# mutebox.net
KiCad netlist of a schematic drawn in EAGLE
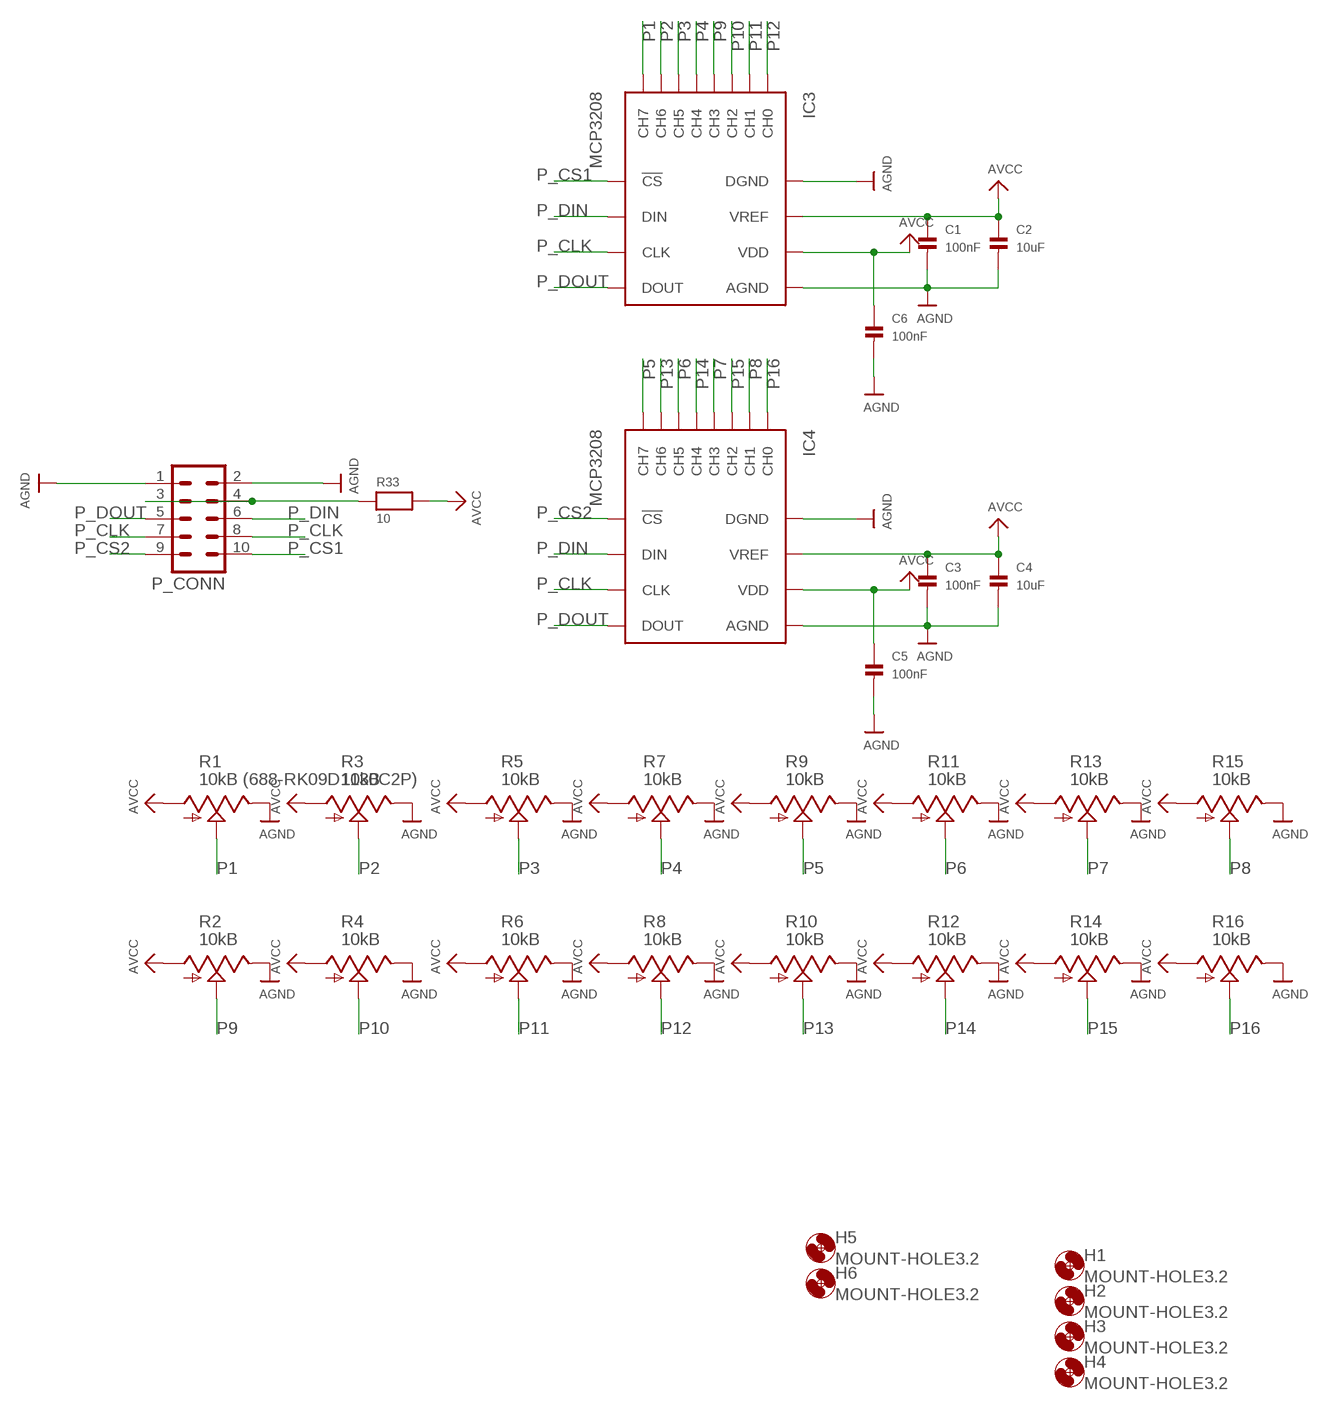
[diagram p0: schematic, sheet 1]
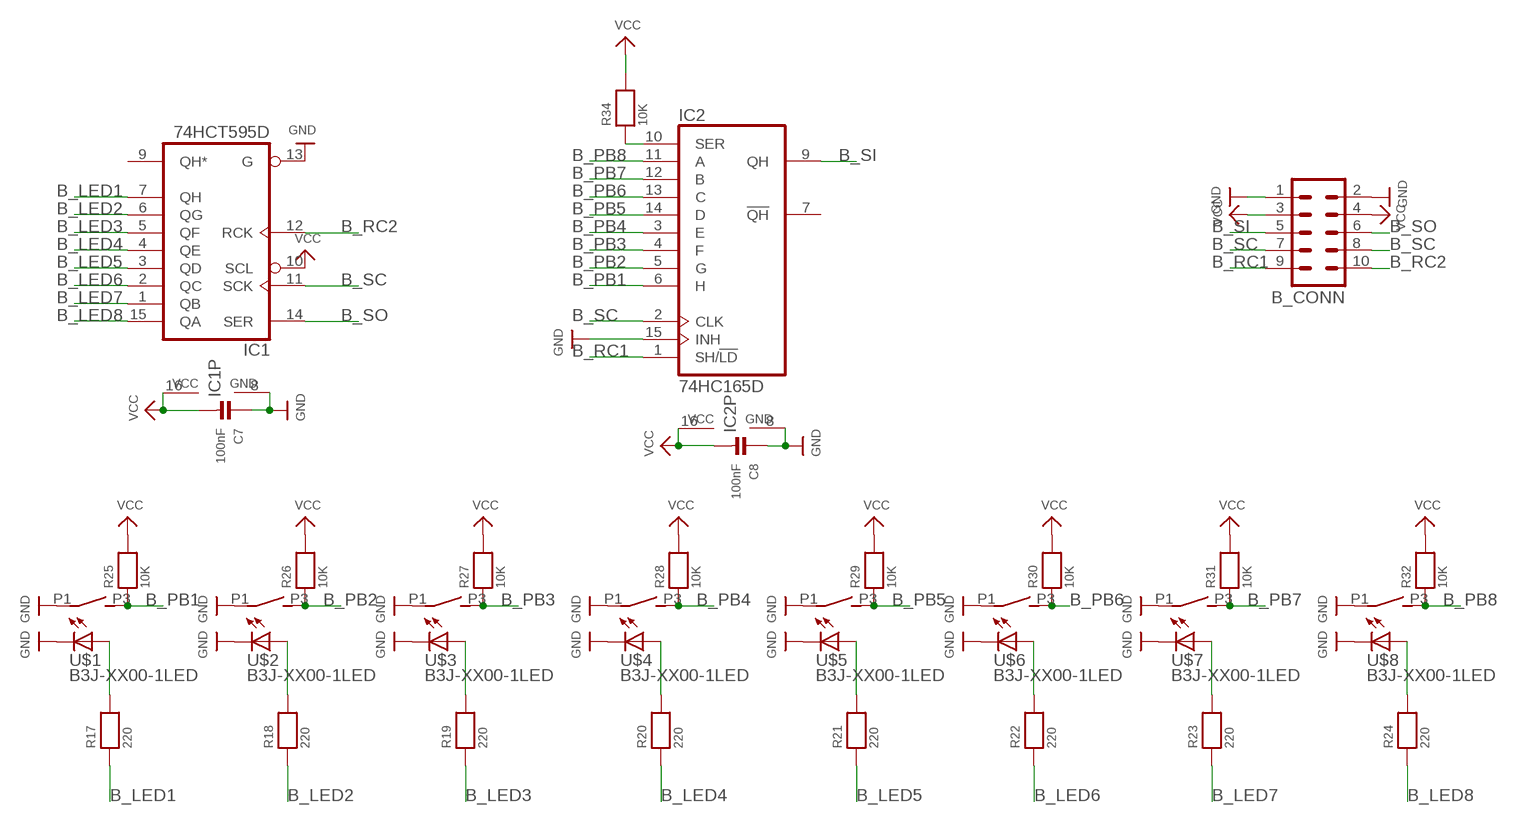
[diagram p1: schematic, sheet 2]

(export (version "E")
  (design (tool "Eeschema 10.0.6"))
  (components
    (comp (ref "C1")
      (value "100nF")
      (footprint "eagle-import:0603")
      (libsource (lib "eagle-import") (part "CAP_CERAMIC0603"))
    )
    (comp (ref "C2")
      (value "10uF")
      (footprint "eagle-import:_0805")
      (libsource (lib "eagle-import") (part "CAP_CERAMIC_0805"))
    )
    (comp (ref "C3")
      (value "100nF")
      (footprint "eagle-import:0603")
      (libsource (lib "eagle-import") (part "CAP_CERAMIC0603"))
    )
    (comp (ref "C4")
      (value "10uF")
      (footprint "eagle-import:_0805")
      (libsource (lib "eagle-import") (part "CAP_CERAMIC_0805"))
    )
    (comp (ref "C5")
      (value "100nF")
      (footprint "eagle-import:0603")
      (libsource (lib "eagle-import") (part "CAP_CERAMIC0603"))
    )
    (comp (ref "C6")
      (value "100nF")
      (footprint "eagle-import:0603")
      (libsource (lib "eagle-import") (part "CAP_CERAMIC0603"))
    )
    (comp (ref "H1")
      (value "MOUNT-HOLE3.2")
      (footprint "eagle-import:3,2")
      (libsource (lib "eagle-import") (part "MOUNT-HOLE3.2"))
    )
    (comp (ref "H2")
      (value "MOUNT-HOLE3.2")
      (footprint "eagle-import:3,2")
      (libsource (lib "eagle-import") (part "MOUNT-HOLE3.2"))
    )
    (comp (ref "H3")
      (value "MOUNT-HOLE3.2")
      (footprint "eagle-import:3,2")
      (libsource (lib "eagle-import") (part "MOUNT-HOLE3.2"))
    )
    (comp (ref "H4")
      (value "MOUNT-HOLE3.2")
      (footprint "eagle-import:3,2")
      (libsource (lib "eagle-import") (part "MOUNT-HOLE3.2"))
    )
    (comp (ref "H5")
      (value "MOUNT-HOLE3.2")
      (footprint "eagle-import:3,2")
      (libsource (lib "eagle-import") (part "MOUNT-HOLE3.2"))
    )
    (comp (ref "H6")
      (value "MOUNT-HOLE3.2")
      (footprint "eagle-import:3,2")
      (libsource (lib "eagle-import") (part "MOUNT-HOLE3.2"))
    )
    (comp (ref "IC3")
      (value "MCP3208")
      (footprint "eagle-import:PDIP16")
      (libsource (lib "eagle-import") (part "21298E"))
    )
    (comp (ref "IC4")
      (value "MCP3208")
      (footprint "eagle-import:PDIP16")
      (libsource (lib "eagle-import") (part "21298E"))
    )
    (comp (ref "P_CONN")
      (value "ML10")
      (footprint "eagle-import:ML10")
      (libsource (lib "eagle-import") (part "ML10"))
    )
    (comp (ref "R1")
      (value "10kB (688-RK09D1130C2P)")
      (footprint "eagle-import:ALPS_POT_VERTICAL_PS")
      (libsource (lib "eagle-import") (part "POT_USVERTICAL_PS"))
    )
    (comp (ref "R2")
      (value "10kB")
      (footprint "eagle-import:ALPS_POT_VERTICAL_PS")
      (libsource (lib "eagle-import") (part "POT_USVERTICAL_PS"))
    )
    (comp (ref "R3")
      (value "10kB")
      (footprint "eagle-import:ALPS_POT_VERTICAL_PS")
      (libsource (lib "eagle-import") (part "POT_USVERTICAL_PS"))
    )
    (comp (ref "R4")
      (value "10kB")
      (footprint "eagle-import:ALPS_POT_VERTICAL_PS")
      (libsource (lib "eagle-import") (part "POT_USVERTICAL_PS"))
    )
    (comp (ref "R5")
      (value "10kB")
      (footprint "eagle-import:ALPS_POT_VERTICAL_PS")
      (libsource (lib "eagle-import") (part "POT_USVERTICAL_PS"))
    )
    (comp (ref "R6")
      (value "10kB")
      (footprint "eagle-import:ALPS_POT_VERTICAL_PS")
      (libsource (lib "eagle-import") (part "POT_USVERTICAL_PS"))
    )
    (comp (ref "R7")
      (value "10kB")
      (footprint "eagle-import:ALPS_POT_VERTICAL_PS")
      (libsource (lib "eagle-import") (part "POT_USVERTICAL_PS"))
    )
    (comp (ref "R8")
      (value "10kB")
      (footprint "eagle-import:ALPS_POT_VERTICAL_PS")
      (libsource (lib "eagle-import") (part "POT_USVERTICAL_PS"))
    )
    (comp (ref "R9")
      (value "10kB")
      (footprint "eagle-import:ALPS_POT_VERTICAL_PS")
      (libsource (lib "eagle-import") (part "POT_USVERTICAL_PS"))
    )
    (comp (ref "R10")
      (value "10kB")
      (footprint "eagle-import:ALPS_POT_VERTICAL_PS")
      (libsource (lib "eagle-import") (part "POT_USVERTICAL_PS"))
    )
    (comp (ref "R11")
      (value "10kB")
      (footprint "eagle-import:ALPS_POT_VERTICAL_PS")
      (libsource (lib "eagle-import") (part "POT_USVERTICAL_PS"))
    )
    (comp (ref "R12")
      (value "10kB")
      (footprint "eagle-import:ALPS_POT_VERTICAL_PS")
      (libsource (lib "eagle-import") (part "POT_USVERTICAL_PS"))
    )
    (comp (ref "R13")
      (value "10kB")
      (footprint "eagle-import:ALPS_POT_VERTICAL_PS")
      (libsource (lib "eagle-import") (part "POT_USVERTICAL_PS"))
    )
    (comp (ref "R14")
      (value "10kB")
      (footprint "eagle-import:ALPS_POT_VERTICAL_PS")
      (libsource (lib "eagle-import") (part "POT_USVERTICAL_PS"))
    )
    (comp (ref "R15")
      (value "10kB")
      (footprint "eagle-import:ALPS_POT_VERTICAL_PS")
      (libsource (lib "eagle-import") (part "POT_USVERTICAL_PS"))
    )
    (comp (ref "R16")
      (value "10kB")
      (footprint "eagle-import:ALPS_POT_VERTICAL_PS")
      (libsource (lib "eagle-import") (part "POT_USVERTICAL_PS"))
    )
    (comp (ref "R33")
      (value "10")
      (footprint "eagle-import:_0805")
      (libsource (lib "eagle-import") (part "RESISTOR_0805"))
    )
    (comp (ref "B_CONN")
      (value "ML10")
      (footprint "eagle-import:ML10")
      (libsource (lib "eagle-import") (part "ML10"))
    )
    (comp (ref "C7")
      (value "100nF")
      (footprint "eagle-import:0603")
      (libsource (lib "eagle-import") (part "CAP_CERAMIC0603"))
    )
    (comp (ref "C8")
      (value "100nF")
      (footprint "eagle-import:0603")
      (libsource (lib "eagle-import") (part "CAP_CERAMIC0603"))
    )
    (comp (ref "IC1")
      (value "74HCT595D")
      (footprint "eagle-import:SO16")
      (libsource (lib "eagle-import") (part "74595DHCT"))
    )
    (comp (ref "IC2")
      (value "74HC165D")
      (footprint "eagle-import:SO16")
      (libsource (lib "eagle-import") (part "74165DHC"))
    )
    (comp (ref "R17")
      (value "220")
      (footprint "eagle-import:_0603")
      (libsource (lib "eagle-import") (part "RESISTOR_0603"))
    )
    (comp (ref "R18")
      (value "220")
      (footprint "eagle-import:_0603")
      (libsource (lib "eagle-import") (part "RESISTOR_0603"))
    )
    (comp (ref "R19")
      (value "220")
      (footprint "eagle-import:_0603")
      (libsource (lib "eagle-import") (part "RESISTOR_0603"))
    )
    (comp (ref "R20")
      (value "220")
      (footprint "eagle-import:_0603")
      (libsource (lib "eagle-import") (part "RESISTOR_0603"))
    )
    (comp (ref "R21")
      (value "220")
      (footprint "eagle-import:_0603")
      (libsource (lib "eagle-import") (part "RESISTOR_0603"))
    )
    (comp (ref "R22")
      (value "220")
      (footprint "eagle-import:_0603")
      (libsource (lib "eagle-import") (part "RESISTOR_0603"))
    )
    (comp (ref "R23")
      (value "220")
      (footprint "eagle-import:_0603")
      (libsource (lib "eagle-import") (part "RESISTOR_0603"))
    )
    (comp (ref "R24")
      (value "220")
      (footprint "eagle-import:_0603")
      (libsource (lib "eagle-import") (part "RESISTOR_0603"))
    )
    (comp (ref "R25")
      (value "10K")
      (footprint "eagle-import:_0603")
      (libsource (lib "eagle-import") (part "RESISTOR_0603"))
    )
    (comp (ref "R26")
      (value "10K")
      (footprint "eagle-import:_0603")
      (libsource (lib "eagle-import") (part "RESISTOR_0603"))
    )
    (comp (ref "R27")
      (value "10K")
      (footprint "eagle-import:_0603")
      (libsource (lib "eagle-import") (part "RESISTOR_0603"))
    )
    (comp (ref "R28")
      (value "10K")
      (footprint "eagle-import:_0603")
      (libsource (lib "eagle-import") (part "RESISTOR_0603"))
    )
    (comp (ref "R29")
      (value "10K")
      (footprint "eagle-import:_0603")
      (libsource (lib "eagle-import") (part "RESISTOR_0603"))
    )
    (comp (ref "R30")
      (value "10K")
      (footprint "eagle-import:_0603")
      (libsource (lib "eagle-import") (part "RESISTOR_0603"))
    )
    (comp (ref "R31")
      (value "10K")
      (footprint "eagle-import:_0603")
      (libsource (lib "eagle-import") (part "RESISTOR_0603"))
    )
    (comp (ref "R32")
      (value "10K")
      (footprint "eagle-import:_0603")
      (libsource (lib "eagle-import") (part "RESISTOR_0603"))
    )
    (comp (ref "R34")
      (value "10K")
      (footprint "eagle-import:_0603")
      (libsource (lib "eagle-import") (part "RESISTOR_0603"))
    )
    (comp (ref "U$1")
      (value "B3J-XX00-1LED")
      (footprint "eagle-import:B3J-XX00-1LED")
      (libsource (lib "eagle-import") (part "B3J-XX00-1LED"))
    )
    (comp (ref "U$2")
      (value "B3J-XX00-1LED")
      (footprint "eagle-import:B3J-XX00-1LED")
      (libsource (lib "eagle-import") (part "B3J-XX00-1LED"))
    )
    (comp (ref "U$3")
      (value "B3J-XX00-1LED")
      (footprint "eagle-import:B3J-XX00-1LED")
      (libsource (lib "eagle-import") (part "B3J-XX00-1LED"))
    )
    (comp (ref "U$4")
      (value "B3J-XX00-1LED")
      (footprint "eagle-import:B3J-XX00-1LED")
      (libsource (lib "eagle-import") (part "B3J-XX00-1LED"))
    )
    (comp (ref "U$5")
      (value "B3J-XX00-1LED")
      (footprint "eagle-import:B3J-XX00-1LED")
      (libsource (lib "eagle-import") (part "B3J-XX00-1LED"))
    )
    (comp (ref "U$6")
      (value "B3J-XX00-1LED")
      (footprint "eagle-import:B3J-XX00-1LED")
      (libsource (lib "eagle-import") (part "B3J-XX00-1LED"))
    )
    (comp (ref "U$7")
      (value "B3J-XX00-1LED")
      (footprint "eagle-import:B3J-XX00-1LED")
      (libsource (lib "eagle-import") (part "B3J-XX00-1LED"))
    )
    (comp (ref "U$8")
      (value "B3J-XX00-1LED")
      (footprint "eagle-import:B3J-XX00-1LED")
      (libsource (lib "eagle-import") (part "B3J-XX00-1LED"))
    )
  )
  (nets
    (net (code "1") (name "AGND") (class "Default")
      (node (ref "C1") (pin "2") (pinfunction "P$2_2") (pintype "passive"))
      (node (ref "C2") (pin "2") (pinfunction "P$2_2") (pintype "passive"))
      (node (ref "C3") (pin "2") (pinfunction "P$2_2") (pintype "passive"))
      (node (ref "C4") (pin "2") (pinfunction "P$2_2") (pintype "passive"))
      (node (ref "C5") (pin "2") (pinfunction "P$2_2") (pintype "passive"))
      (node (ref "C6") (pin "2") (pinfunction "P$2_2") (pintype "passive"))
      (node (ref "IC3") (pin "P$14") (pinfunction "AGND_P$14") (pintype "bidirectional"))
      (node (ref "IC3") (pin "P$9") (pinfunction "DGND_P$9") (pintype "bidirectional"))
      (node (ref "IC4") (pin "P$14") (pinfunction "AGND_P$14") (pintype "bidirectional"))
      (node (ref "IC4") (pin "P$9") (pinfunction "DGND_P$9") (pintype "bidirectional"))
      (node (ref "P_CONN") (pin "1") (pinfunction "1_1") (pintype "passive"))
      (node (ref "P_CONN") (pin "2") (pinfunction "2_2") (pintype "passive"))
      (node (ref "R1") (pin "P$1") (pinfunction "E_P$1") (pintype "passive"))
      (node (ref "R10") (pin "P$1") (pinfunction "E_P$1") (pintype "passive"))
      (node (ref "R11") (pin "P$1") (pinfunction "E_P$1") (pintype "passive"))
      (node (ref "R12") (pin "P$1") (pinfunction "E_P$1") (pintype "passive"))
      (node (ref "R13") (pin "P$1") (pinfunction "E_P$1") (pintype "passive"))
      (node (ref "R14") (pin "P$1") (pinfunction "E_P$1") (pintype "passive"))
      (node (ref "R15") (pin "P$1") (pinfunction "E_P$1") (pintype "passive"))
      (node (ref "R16") (pin "P$1") (pinfunction "E_P$1") (pintype "passive"))
      (node (ref "R2") (pin "P$1") (pinfunction "E_P$1") (pintype "passive"))
      (node (ref "R3") (pin "P$1") (pinfunction "E_P$1") (pintype "passive"))
      (node (ref "R4") (pin "P$1") (pinfunction "E_P$1") (pintype "passive"))
      (node (ref "R5") (pin "P$1") (pinfunction "E_P$1") (pintype "passive"))
      (node (ref "R6") (pin "P$1") (pinfunction "E_P$1") (pintype "passive"))
      (node (ref "R7") (pin "P$1") (pinfunction "E_P$1") (pintype "passive"))
      (node (ref "R8") (pin "P$1") (pinfunction "E_P$1") (pintype "passive"))
      (node (ref "R9") (pin "P$1") (pinfunction "E_P$1") (pintype "passive"))
    )
    (net (code "2") (name "AVCC") (class "Default")
      (node (ref "C1") (pin "1") (pinfunction "P$1_1") (pintype "passive"))
      (node (ref "C2") (pin "1") (pinfunction "P$1_1") (pintype "passive"))
      (node (ref "C3") (pin "1") (pinfunction "P$1_1") (pintype "passive"))
      (node (ref "C4") (pin "1") (pinfunction "P$1_1") (pintype "passive"))
      (node (ref "C5") (pin "1") (pinfunction "P$1_1") (pintype "passive"))
      (node (ref "C6") (pin "1") (pinfunction "P$1_1") (pintype "passive"))
      (node (ref "IC3") (pin "P$15") (pinfunction "VREF_P$15") (pintype "bidirectional"))
      (node (ref "IC3") (pin "P$16") (pinfunction "VDD_P$16") (pintype "bidirectional"))
      (node (ref "IC4") (pin "P$15") (pinfunction "VREF_P$15") (pintype "bidirectional"))
      (node (ref "IC4") (pin "P$16") (pinfunction "VDD_P$16") (pintype "bidirectional"))
      (node (ref "R1") (pin "P$3") (pinfunction "A_P$3") (pintype "passive"))
      (node (ref "R10") (pin "P$3") (pinfunction "A_P$3") (pintype "passive"))
      (node (ref "R11") (pin "P$3") (pinfunction "A_P$3") (pintype "passive"))
      (node (ref "R12") (pin "P$3") (pinfunction "A_P$3") (pintype "passive"))
      (node (ref "R13") (pin "P$3") (pinfunction "A_P$3") (pintype "passive"))
      (node (ref "R14") (pin "P$3") (pinfunction "A_P$3") (pintype "passive"))
      (node (ref "R15") (pin "P$3") (pinfunction "A_P$3") (pintype "passive"))
      (node (ref "R16") (pin "P$3") (pinfunction "A_P$3") (pintype "passive"))
      (node (ref "R2") (pin "P$3") (pinfunction "A_P$3") (pintype "passive"))
      (node (ref "R3") (pin "P$3") (pinfunction "A_P$3") (pintype "passive"))
      (node (ref "R33") (pin "2") (pinfunction "2_2") (pintype "passive"))
      (node (ref "R4") (pin "P$3") (pinfunction "A_P$3") (pintype "passive"))
      (node (ref "R5") (pin "P$3") (pinfunction "A_P$3") (pintype "passive"))
      (node (ref "R6") (pin "P$3") (pinfunction "A_P$3") (pintype "passive"))
      (node (ref "R7") (pin "P$3") (pinfunction "A_P$3") (pintype "passive"))
      (node (ref "R8") (pin "P$3") (pinfunction "A_P$3") (pintype "passive"))
      (node (ref "R9") (pin "P$3") (pinfunction "A_P$3") (pintype "passive"))
    )
    (net (code "3") (name "B_LED1") (class "Default")
      (node (ref "IC1") (pin "7") (pinfunction "QH_7") (pintype "tri_state"))
      (node (ref "R17") (pin "1") (pinfunction "1_1") (pintype "passive"))
    )
    (net (code "4") (name "B_LED2") (class "Default")
      (node (ref "IC1") (pin "6") (pinfunction "QG_6") (pintype "tri_state"))
      (node (ref "R18") (pin "1") (pinfunction "1_1") (pintype "passive"))
    )
    (net (code "5") (name "B_LED3") (class "Default")
      (node (ref "IC1") (pin "5") (pinfunction "QF_5") (pintype "tri_state"))
      (node (ref "R19") (pin "1") (pinfunction "1_1") (pintype "passive"))
    )
    (net (code "6") (name "B_LED4") (class "Default")
      (node (ref "IC1") (pin "4") (pinfunction "QE_4") (pintype "tri_state"))
      (node (ref "R20") (pin "1") (pinfunction "1_1") (pintype "passive"))
    )
    (net (code "7") (name "B_LED5") (class "Default")
      (node (ref "IC1") (pin "3") (pinfunction "QD_3") (pintype "tri_state"))
      (node (ref "R21") (pin "1") (pinfunction "1_1") (pintype "passive"))
    )
    (net (code "8") (name "B_LED6") (class "Default")
      (node (ref "IC1") (pin "2") (pinfunction "QC_2") (pintype "tri_state"))
      (node (ref "R22") (pin "1") (pinfunction "1_1") (pintype "passive"))
    )
    (net (code "9") (name "B_LED7") (class "Default")
      (node (ref "IC1") (pin "1") (pinfunction "QB_1") (pintype "tri_state"))
      (node (ref "R23") (pin "1") (pinfunction "1_1") (pintype "passive"))
    )
    (net (code "10") (name "B_LED8") (class "Default")
      (node (ref "IC1") (pin "15") (pinfunction "QA_15") (pintype "tri_state"))
      (node (ref "R24") (pin "1") (pinfunction "1_1") (pintype "passive"))
    )
    (net (code "11") (name "B_PB1") (class "Default")
      (node (ref "IC2") (pin "6") (pinfunction "H_6") (pintype "input"))
      (node (ref "R25") (pin "1") (pinfunction "1_1") (pintype "passive"))
      (node (ref "U$1") (pin "P3") (pinfunction "SW2_P3") (pintype "passive"))
    )
    (net (code "12") (name "B_PB2") (class "Default")
      (node (ref "IC2") (pin "5") (pinfunction "G_5") (pintype "input"))
      (node (ref "R26") (pin "1") (pinfunction "1_1") (pintype "passive"))
      (node (ref "U$2") (pin "P3") (pinfunction "SW2_P3") (pintype "passive"))
    )
    (net (code "13") (name "B_PB3") (class "Default")
      (node (ref "IC2") (pin "4") (pinfunction "F_4") (pintype "input"))
      (node (ref "R27") (pin "1") (pinfunction "1_1") (pintype "passive"))
      (node (ref "U$3") (pin "P3") (pinfunction "SW2_P3") (pintype "passive"))
    )
    (net (code "14") (name "B_PB4") (class "Default")
      (node (ref "IC2") (pin "3") (pinfunction "E_3") (pintype "input"))
      (node (ref "R28") (pin "1") (pinfunction "1_1") (pintype "passive"))
      (node (ref "U$4") (pin "P3") (pinfunction "SW2_P3") (pintype "passive"))
    )
    (net (code "15") (name "B_PB5") (class "Default")
      (node (ref "IC2") (pin "14") (pinfunction "D_14") (pintype "input"))
      (node (ref "R29") (pin "1") (pinfunction "1_1") (pintype "passive"))
      (node (ref "U$5") (pin "P3") (pinfunction "SW2_P3") (pintype "passive"))
    )
    (net (code "16") (name "B_PB6") (class "Default")
      (node (ref "IC2") (pin "13") (pinfunction "C_13") (pintype "input"))
      (node (ref "R30") (pin "1") (pinfunction "1_1") (pintype "passive"))
      (node (ref "U$6") (pin "P3") (pinfunction "SW2_P3") (pintype "passive"))
    )
    (net (code "17") (name "B_PB7") (class "Default")
      (node (ref "IC2") (pin "12") (pinfunction "B_12") (pintype "input"))
      (node (ref "R31") (pin "1") (pinfunction "1_1") (pintype "passive"))
      (node (ref "U$7") (pin "P3") (pinfunction "SW2_P3") (pintype "passive"))
    )
    (net (code "18") (name "B_PB8") (class "Default")
      (node (ref "IC2") (pin "11") (pinfunction "A_11") (pintype "input"))
      (node (ref "R32") (pin "1") (pinfunction "1_1") (pintype "passive"))
      (node (ref "U$8") (pin "P3") (pinfunction "SW2_P3") (pintype "passive"))
    )
    (net (code "19") (name "B_RC1") (class "Default")
      (node (ref "B_CONN") (pin "9") (pinfunction "9_9") (pintype "passive"))
      (node (ref "IC2") (pin "1") (pinfunction "SH/~{LD}_1") (pintype "input"))
    )
    (net (code "20") (name "B_RC2") (class "Default")
      (node (ref "B_CONN") (pin "10") (pinfunction "10_10") (pintype "passive"))
      (node (ref "IC1") (pin "12") (pinfunction "RCK_12") (pintype "input"))
    )
    (net (code "21") (name "B_SC") (class "Default")
      (node (ref "B_CONN") (pin "7") (pinfunction "7_7") (pintype "passive"))
      (node (ref "B_CONN") (pin "8") (pinfunction "8_8") (pintype "passive"))
      (node (ref "IC1") (pin "11") (pinfunction "SCK_11") (pintype "input"))
      (node (ref "IC2") (pin "2") (pinfunction "CLK_2") (pintype "input"))
    )
    (net (code "22") (name "B_SI") (class "Default")
      (node (ref "B_CONN") (pin "5") (pinfunction "5_5") (pintype "passive"))
      (node (ref "IC2") (pin "9") (pinfunction "QH_9") (pintype "output"))
    )
    (net (code "23") (name "B_SO") (class "Default")
      (node (ref "B_CONN") (pin "6") (pinfunction "6_6") (pintype "passive"))
      (node (ref "IC1") (pin "14") (pinfunction "SER_14") (pintype "input"))
    )
    (net (code "24") (name "GND") (class "Default")
      (node (ref "B_CONN") (pin "1") (pinfunction "1_1") (pintype "passive"))
      (node (ref "B_CONN") (pin "2") (pinfunction "2_2") (pintype "passive"))
      (node (ref "C7") (pin "1") (pinfunction "P$1_1") (pintype "passive"))
      (node (ref "C8") (pin "1") (pinfunction "P$1_1") (pintype "passive"))
      (node (ref "IC1") (pin "13") (pinfunction "G_13") (pintype "input"))
      (node (ref "IC1") (pin "8") (pinfunction "GND_8") (pintype "power_in"))
      (node (ref "IC2") (pin "15") (pinfunction "INH_15") (pintype "input"))
      (node (ref "IC2") (pin "8") (pinfunction "GND_8") (pintype "power_in"))
      (node (ref "U$1") (pin "LED-") (pinfunction "LED-_LED-") (pintype "passive"))
      (node (ref "U$1") (pin "P1") (pinfunction "SW1_P1") (pintype "passive"))
      (node (ref "U$2") (pin "LED-") (pinfunction "LED-_LED-") (pintype "passive"))
      (node (ref "U$2") (pin "P1") (pinfunction "SW1_P1") (pintype "passive"))
      (node (ref "U$3") (pin "LED-") (pinfunction "LED-_LED-") (pintype "passive"))
      (node (ref "U$3") (pin "P1") (pinfunction "SW1_P1") (pintype "passive"))
      (node (ref "U$4") (pin "LED-") (pinfunction "LED-_LED-") (pintype "passive"))
      (node (ref "U$4") (pin "P1") (pinfunction "SW1_P1") (pintype "passive"))
      (node (ref "U$5") (pin "LED-") (pinfunction "LED-_LED-") (pintype "passive"))
      (node (ref "U$5") (pin "P1") (pinfunction "SW1_P1") (pintype "passive"))
      (node (ref "U$6") (pin "LED-") (pinfunction "LED-_LED-") (pintype "passive"))
      (node (ref "U$6") (pin "P1") (pinfunction "SW1_P1") (pintype "passive"))
      (node (ref "U$7") (pin "LED-") (pinfunction "LED-_LED-") (pintype "passive"))
      (node (ref "U$7") (pin "P1") (pinfunction "SW1_P1") (pintype "passive"))
      (node (ref "U$8") (pin "LED-") (pinfunction "LED-_LED-") (pintype "passive"))
      (node (ref "U$8") (pin "P1") (pinfunction "SW1_P1") (pintype "passive"))
    )
    (net (code "25") (name "Net-(IC2A-SER)") (class "Default")
      (node (ref "IC2") (pin "10") (pinfunction "SER_10") (pintype "input"))
      (node (ref "R34") (pin "1") (pinfunction "1_1") (pintype "passive"))
    )
    (net (code "26") (name "Net-(P_CONN-Pad3)") (class "Default")
      (node (ref "P_CONN") (pin "3") (pinfunction "3_3") (pintype "passive"))
      (node (ref "P_CONN") (pin "4") (pinfunction "4_4") (pintype "passive"))
      (node (ref "R33") (pin "1") (pinfunction "1_1") (pintype "passive"))
    )
    (net (code "27") (name "Net-(R17-Pad2)") (class "Default")
      (node (ref "R17") (pin "2") (pinfunction "2_2") (pintype "passive"))
      (node (ref "U$1") (pin "LED+") (pinfunction "LED+_LED+") (pintype "passive"))
    )
    (net (code "28") (name "Net-(R18-Pad2)") (class "Default")
      (node (ref "R18") (pin "2") (pinfunction "2_2") (pintype "passive"))
      (node (ref "U$2") (pin "LED+") (pinfunction "LED+_LED+") (pintype "passive"))
    )
    (net (code "29") (name "Net-(R19-Pad2)") (class "Default")
      (node (ref "R19") (pin "2") (pinfunction "2_2") (pintype "passive"))
      (node (ref "U$3") (pin "LED+") (pinfunction "LED+_LED+") (pintype "passive"))
    )
    (net (code "30") (name "Net-(R20-Pad2)") (class "Default")
      (node (ref "R20") (pin "2") (pinfunction "2_2") (pintype "passive"))
      (node (ref "U$4") (pin "LED+") (pinfunction "LED+_LED+") (pintype "passive"))
    )
    (net (code "31") (name "Net-(R21-Pad2)") (class "Default")
      (node (ref "R21") (pin "2") (pinfunction "2_2") (pintype "passive"))
      (node (ref "U$5") (pin "LED+") (pinfunction "LED+_LED+") (pintype "passive"))
    )
    (net (code "32") (name "Net-(R22-Pad2)") (class "Default")
      (node (ref "R22") (pin "2") (pinfunction "2_2") (pintype "passive"))
      (node (ref "U$6") (pin "LED+") (pinfunction "LED+_LED+") (pintype "passive"))
    )
    (net (code "33") (name "Net-(R23-Pad2)") (class "Default")
      (node (ref "R23") (pin "2") (pinfunction "2_2") (pintype "passive"))
      (node (ref "U$7") (pin "LED+") (pinfunction "LED+_LED+") (pintype "passive"))
    )
    (net (code "34") (name "Net-(R24-Pad2)") (class "Default")
      (node (ref "R24") (pin "2") (pinfunction "2_2") (pintype "passive"))
      (node (ref "U$8") (pin "LED+") (pinfunction "LED+_LED+") (pintype "passive"))
    )
    (net (code "35") (name "P1") (class "Default")
      (node (ref "IC3") (pin "P$8") (pinfunction "CH7_P$8") (pintype "bidirectional"))
      (node (ref "R1") (pin "P$2") (pinfunction "S_P$2") (pintype "passive"))
    )
    (net (code "36") (name "P2") (class "Default")
      (node (ref "IC3") (pin "P$7") (pinfunction "CH6_P$7") (pintype "bidirectional"))
      (node (ref "R3") (pin "P$2") (pinfunction "S_P$2") (pintype "passive"))
    )
    (net (code "37") (name "P3") (class "Default")
      (node (ref "IC3") (pin "P$6") (pinfunction "CH5_P$6") (pintype "bidirectional"))
      (node (ref "R5") (pin "P$2") (pinfunction "S_P$2") (pintype "passive"))
    )
    (net (code "38") (name "P4") (class "Default")
      (node (ref "IC3") (pin "P$5") (pinfunction "CH4_P$5") (pintype "bidirectional"))
      (node (ref "R7") (pin "P$2") (pinfunction "S_P$2") (pintype "passive"))
    )
    (net (code "39") (name "P5") (class "Default")
      (node (ref "IC4") (pin "P$8") (pinfunction "CH7_P$8") (pintype "bidirectional"))
      (node (ref "R9") (pin "P$2") (pinfunction "S_P$2") (pintype "passive"))
    )
    (net (code "40") (name "P6") (class "Default")
      (node (ref "IC4") (pin "P$6") (pinfunction "CH5_P$6") (pintype "bidirectional"))
      (node (ref "R11") (pin "P$2") (pinfunction "S_P$2") (pintype "passive"))
    )
    (net (code "41") (name "P7") (class "Default")
      (node (ref "IC4") (pin "P$4") (pinfunction "CH3_P$4") (pintype "bidirectional"))
      (node (ref "R13") (pin "P$2") (pinfunction "S_P$2") (pintype "passive"))
    )
    (net (code "42") (name "P8") (class "Default")
      (node (ref "IC4") (pin "P$2") (pinfunction "CH1_P$2") (pintype "bidirectional"))
      (node (ref "R15") (pin "P$2") (pinfunction "S_P$2") (pintype "passive"))
    )
    (net (code "43") (name "P9") (class "Default")
      (node (ref "IC3") (pin "P$4") (pinfunction "CH3_P$4") (pintype "bidirectional"))
      (node (ref "R2") (pin "P$2") (pinfunction "S_P$2") (pintype "passive"))
    )
    (net (code "44") (name "P10") (class "Default")
      (node (ref "IC3") (pin "P$3") (pinfunction "CH2_P$3") (pintype "bidirectional"))
      (node (ref "R4") (pin "P$2") (pinfunction "S_P$2") (pintype "passive"))
    )
    (net (code "45") (name "P11") (class "Default")
      (node (ref "IC3") (pin "P$2") (pinfunction "CH1_P$2") (pintype "bidirectional"))
      (node (ref "R6") (pin "P$2") (pinfunction "S_P$2") (pintype "passive"))
    )
    (net (code "46") (name "P12") (class "Default")
      (node (ref "IC3") (pin "P$1") (pinfunction "CH0_P$1") (pintype "bidirectional"))
      (node (ref "R8") (pin "P$2") (pinfunction "S_P$2") (pintype "passive"))
    )
    (net (code "47") (name "P13") (class "Default")
      (node (ref "IC4") (pin "P$7") (pinfunction "CH6_P$7") (pintype "bidirectional"))
      (node (ref "R10") (pin "P$2") (pinfunction "S_P$2") (pintype "passive"))
    )
    (net (code "48") (name "P14") (class "Default")
      (node (ref "IC4") (pin "P$5") (pinfunction "CH4_P$5") (pintype "bidirectional"))
      (node (ref "R12") (pin "P$2") (pinfunction "S_P$2") (pintype "passive"))
    )
    (net (code "49") (name "P15") (class "Default")
      (node (ref "IC4") (pin "P$3") (pinfunction "CH2_P$3") (pintype "bidirectional"))
      (node (ref "R14") (pin "P$2") (pinfunction "S_P$2") (pintype "passive"))
    )
    (net (code "50") (name "P16") (class "Default")
      (node (ref "IC4") (pin "P$1") (pinfunction "CH0_P$1") (pintype "bidirectional"))
      (node (ref "R16") (pin "P$2") (pinfunction "S_P$2") (pintype "passive"))
    )
    (net (code "51") (name "P_CLK") (class "Default")
      (node (ref "IC3") (pin "P$13") (pinfunction "CLK_P$13") (pintype "bidirectional"))
      (node (ref "IC4") (pin "P$13") (pinfunction "CLK_P$13") (pintype "bidirectional"))
      (node (ref "P_CONN") (pin "7") (pinfunction "7_7") (pintype "passive"))
      (node (ref "P_CONN") (pin "8") (pinfunction "8_8") (pintype "passive"))
    )
    (net (code "52") (name "P_CS1") (class "Default")
      (node (ref "IC3") (pin "P$10") (pinfunction "~{CS}_P$10") (pintype "bidirectional"))
      (node (ref "P_CONN") (pin "10") (pinfunction "10_10") (pintype "passive"))
    )
    (net (code "53") (name "P_CS2") (class "Default")
      (node (ref "IC4") (pin "P$10") (pinfunction "~{CS}_P$10") (pintype "bidirectional"))
      (node (ref "P_CONN") (pin "9") (pinfunction "9_9") (pintype "passive"))
    )
    (net (code "54") (name "P_DIN") (class "Default")
      (node (ref "IC3") (pin "P$11") (pinfunction "DIN_P$11") (pintype "bidirectional"))
      (node (ref "IC4") (pin "P$11") (pinfunction "DIN_P$11") (pintype "bidirectional"))
      (node (ref "P_CONN") (pin "6") (pinfunction "6_6") (pintype "passive"))
    )
    (net (code "55") (name "P_DOUT") (class "Default")
      (node (ref "IC3") (pin "P$12") (pinfunction "DOUT_P$12") (pintype "bidirectional"))
      (node (ref "IC4") (pin "P$12") (pinfunction "DOUT_P$12") (pintype "bidirectional"))
      (node (ref "P_CONN") (pin "5") (pinfunction "5_5") (pintype "passive"))
    )
    (net (code "56") (name "VCC") (class "Default")
      (node (ref "B_CONN") (pin "3") (pinfunction "3_3") (pintype "passive"))
      (node (ref "B_CONN") (pin "4") (pinfunction "4_4") (pintype "passive"))
      (node (ref "C7") (pin "2") (pinfunction "P$2_2") (pintype "passive"))
      (node (ref "C8") (pin "2") (pinfunction "P$2_2") (pintype "passive"))
      (node (ref "IC1") (pin "10") (pinfunction "SCL_10") (pintype "input"))
      (node (ref "IC1") (pin "16") (pinfunction "VCC_16") (pintype "power_in"))
      (node (ref "IC2") (pin "16") (pinfunction "VCC_16") (pintype "power_in"))
      (node (ref "R25") (pin "2") (pinfunction "2_2") (pintype "passive"))
      (node (ref "R26") (pin "2") (pinfunction "2_2") (pintype "passive"))
      (node (ref "R27") (pin "2") (pinfunction "2_2") (pintype "passive"))
      (node (ref "R28") (pin "2") (pinfunction "2_2") (pintype "passive"))
      (node (ref "R29") (pin "2") (pinfunction "2_2") (pintype "passive"))
      (node (ref "R30") (pin "2") (pinfunction "2_2") (pintype "passive"))
      (node (ref "R31") (pin "2") (pinfunction "2_2") (pintype "passive"))
      (node (ref "R32") (pin "2") (pinfunction "2_2") (pintype "passive"))
      (node (ref "R34") (pin "2") (pinfunction "2_2") (pintype "passive"))
    )
    (net (code "57") (name "unconnected-(IC1A-QH*-Pad9)") (class "Default")
      (node (ref "IC1") (pin "9") (pinfunction "QH*_9") (pintype "tri_state"))
    )
    (net (code "58") (name "unconnected-(IC2A-~{QH}-Pad7)") (class "Default")
      (node (ref "IC2") (pin "7") (pinfunction "~{QH}_7") (pintype "output"))
    )
  )
)
